# beaconBoard.net
KiCad netlist of a schematic drawn in EAGLE
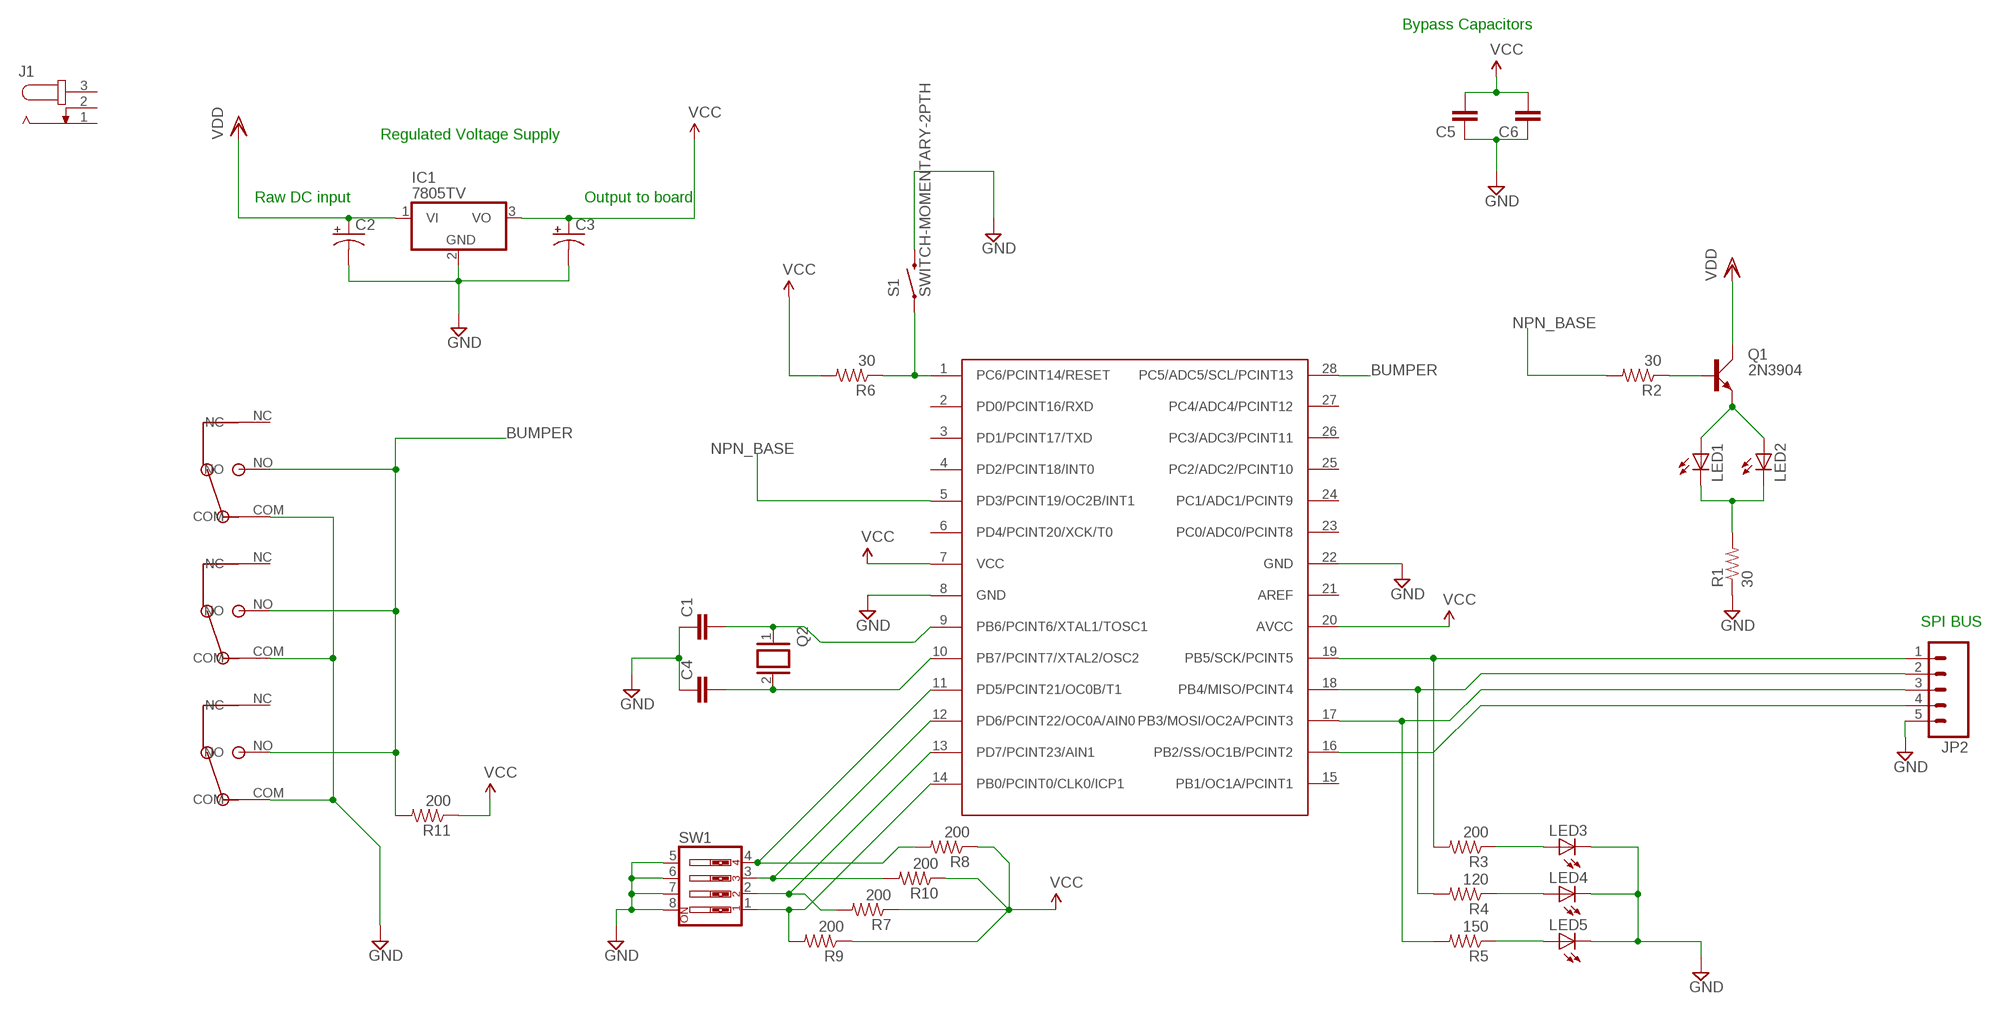
[diagram p0: schematic, sheet 1]

(export (version "E")
  (design (tool "Eeschema 10.0.6"))
  (components
    (comp (ref "C1")
      (value "CAPPTH")
      (footprint "eagle-import:CAP-PTH-SMALL")
      (libsource (lib "eagle-import") (part "CAPPTH"))
    )
    (comp (ref "C2")
      (value "CAP_POLPTH2")
      (footprint "eagle-import:CPOL-RADIAL-10UF-25V")
      (libsource (lib "eagle-import") (part "CAP_POLPTH2"))
    )
    (comp (ref "C3")
      (value "CAP_POLPTH2")
      (footprint "eagle-import:CPOL-RADIAL-10UF-25V")
      (libsource (lib "eagle-import") (part "CAP_POLPTH2"))
    )
    (comp (ref "C4")
      (value "CAPPTH")
      (footprint "eagle-import:CAP-PTH-SMALL")
      (libsource (lib "eagle-import") (part "CAPPTH"))
    )
    (comp (ref "C5")
      (value "CAPPTH")
      (footprint "eagle-import:CAP-PTH-SMALL")
      (libsource (lib "eagle-import") (part "CAPPTH"))
    )
    (comp (ref "C6")
      (value "CAPPTH")
      (footprint "eagle-import:CAP-PTH-SMALL")
      (libsource (lib "eagle-import") (part "CAPPTH"))
    )
    (comp (ref "IC1")
      (value "7805TV")
      (footprint "eagle-import:TO220V")
      (libsource (lib "eagle-import") (part "78TV05"))
    )
    (comp (ref "J1")
      (value "JACK-PLUG1")
      (footprint "eagle-import:SPC4078")
      (libsource (lib "eagle-import") (part "JACK-PLUG1"))
    )
    (comp (ref "JP2")
      (value "M05LOCK_LONGPADS")
      (footprint "eagle-import:1X05_LOCK_LONGPADS")
      (libsource (lib "eagle-import") (part "M05LOCK_LONGPADS"))
    )
    (comp (ref "LED1")
      (value "LED-2AC-CP41B-WES")
      (footprint "eagle-import:CP41B")
      (libsource (lib "eagle-import") (part "LED-2AC-CP41B-WES"))
    )
    (comp (ref "LED2")
      (value "LED-2AC-CP41B-WES")
      (footprint "eagle-import:CP41B")
      (libsource (lib "eagle-import") (part "LED-2AC-CP41B-WES"))
    )
    (comp (ref "LED3")
      (value "LED5MM")
      (footprint "eagle-import:LED5MM")
      (libsource (lib "eagle-import") (part "LED5MM"))
    )
    (comp (ref "LED4")
      (value "LED5MM")
      (footprint "eagle-import:LED5MM")
      (libsource (lib "eagle-import") (part "LED5MM"))
    )
    (comp (ref "LED5")
      (value "LED5MM")
      (footprint "eagle-import:LED5MM")
      (libsource (lib "eagle-import") (part "LED5MM"))
    )
    (comp (ref "Q1")
      (value "2N3904")
      (footprint "eagle-import:TO92D")
      (libsource (lib "eagle-import") (part "2N3904"))
    )
    (comp (ref "Q2")
      (value "XTAL/S")
      (footprint "eagle-import:QS")
      (libsource (lib "eagle-import") (part "XTAL/S"))
    )
    (comp (ref "R1")
      (value "30")
      (footprint "eagle-import:AXIAL-0.4")
      (libsource (lib "eagle-import") (part "RESISTORPTH-1/4W"))
    )
    (comp (ref "R2")
      (value "30")
      (footprint "eagle-import:AXIAL-0.4")
      (libsource (lib "eagle-import") (part "RESISTORPTH-1/4W"))
    )
    (comp (ref "R3")
      (value "200")
      (footprint "eagle-import:AXIAL-0.4")
      (libsource (lib "eagle-import") (part "RESISTORPTH-1/4W"))
    )
    (comp (ref "R4")
      (value "120")
      (footprint "eagle-import:AXIAL-0.4")
      (libsource (lib "eagle-import") (part "RESISTORPTH-1/4W"))
    )
    (comp (ref "R5")
      (value "150")
      (footprint "eagle-import:AXIAL-0.4")
      (libsource (lib "eagle-import") (part "RESISTORPTH-1/4W"))
    )
    (comp (ref "R6")
      (value "30")
      (footprint "eagle-import:AXIAL-0.4")
      (libsource (lib "eagle-import") (part "RESISTORPTH-1/4W"))
    )
    (comp (ref "R7")
      (value "200")
      (footprint "eagle-import:AXIAL-0.4")
      (libsource (lib "eagle-import") (part "RESISTORPTH-1/4W"))
    )
    (comp (ref "R8")
      (value "200")
      (footprint "eagle-import:AXIAL-0.4")
      (libsource (lib "eagle-import") (part "RESISTORPTH-1/4W"))
    )
    (comp (ref "R9")
      (value "200")
      (footprint "eagle-import:AXIAL-0.4")
      (libsource (lib "eagle-import") (part "RESISTORPTH-1/4W"))
    )
    (comp (ref "R10")
      (value "200")
      (footprint "eagle-import:AXIAL-0.4")
      (libsource (lib "eagle-import") (part "RESISTORPTH-1/4W"))
    )
    (comp (ref "R11")
      (value "200")
      (footprint "eagle-import:AXIAL-0.4")
      (libsource (lib "eagle-import") (part "RESISTORPTH-1/4W"))
    )
    (comp (ref "S1")
      (value "SWITCH-MOMENTARY-2PTH")
      (footprint "eagle-import:TACTILE-PTH")
      (libsource (lib "eagle-import") (part "SWITCH-MOMENTARY-2PTH"))
    )
    (comp (ref "SW1")
      (value "SW_DIP-4")
      (footprint "eagle-import:EDG-04")
      (libsource (lib "eagle-import") (part "SW_DIP-4"))
    )
    (comp (ref "U$1")
      (value "DF2-L")
      (footprint "eagle-import:D2F-L")
      (libsource (lib "eagle-import") (part "DF2-L"))
    )
    (comp (ref "U$2")
      (value "DF2-L")
      (footprint "eagle-import:D2F-L")
      (libsource (lib "eagle-import") (part "DF2-L"))
    )
    (comp (ref "U$3")
      (value "DF2-L")
      (footprint "eagle-import:D2F-L")
      (libsource (lib "eagle-import") (part "DF2-L"))
    )
    (comp (ref "U$4")
      (value "ATMEGA328")
      (footprint "eagle-import:DIL28-3")
      (libsource (lib "eagle-import") (part "ATMEGA328"))
    )
  )
  (nets
    (net (code "1") (name "/BUMPER") (class "Default")
      (node (ref "R11") (pin "P$2") (pinfunction "2_P$2") (pintype "passive"))
      (node (ref "U$1") (pin "NO") (pinfunction "NO_NO") (pintype "bidirectional"))
      (node (ref "U$2") (pin "NO") (pinfunction "NO_NO") (pintype "bidirectional"))
      (node (ref "U$3") (pin "NO") (pinfunction "NO_NO") (pintype "bidirectional"))
      (node (ref "U$4") (pin "28") (pinfunction "PC5/ADC5/SCL/PCINT13_28") (pintype "bidirectional"))
    )
    (net (code "2") (name "/NPN_BASE") (class "Default")
      (node (ref "R2") (pin "P$2") (pinfunction "2_P$2") (pintype "passive"))
      (node (ref "U$4") (pin "5") (pinfunction "PD3/PCINT19/OC2B/INT1_5") (pintype "bidirectional"))
    )
    (net (code "3") (name "GND") (class "Default")
      (node (ref "C1") (pin "1") (pinfunction "1_1") (pintype "passive"))
      (node (ref "C2") (pin "2") (pinfunction "-_2") (pintype "passive"))
      (node (ref "C3") (pin "2") (pinfunction "-_2") (pintype "passive"))
      (node (ref "C4") (pin "1") (pinfunction "1_1") (pintype "passive"))
      (node (ref "C5") (pin "1") (pinfunction "1_1") (pintype "passive"))
      (node (ref "C6") (pin "1") (pinfunction "1_1") (pintype "passive"))
      (node (ref "IC1") (pin "2") (pinfunction "GND_2") (pintype "passive"))
      (node (ref "JP2") (pin "5") (pinfunction "5_5") (pintype "passive"))
      (node (ref "LED3") (pin "K") (pinfunction "C_K") (pintype "passive"))
      (node (ref "LED4") (pin "K") (pinfunction "C_K") (pintype "passive"))
      (node (ref "LED5") (pin "K") (pinfunction "C_K") (pintype "passive"))
      (node (ref "R1") (pin "P$1") (pinfunction "1_P$1") (pintype "passive"))
      (node (ref "S1") (pin "3") (pinfunction "2_3") (pintype "passive"))
      (node (ref "SW1") (pin "5") (pinfunction "5_5") (pintype "passive"))
      (node (ref "SW1") (pin "6") (pinfunction "6_6") (pintype "passive"))
      (node (ref "SW1") (pin "7") (pinfunction "7_7") (pintype "passive"))
      (node (ref "SW1") (pin "8") (pinfunction "8_8") (pintype "passive"))
      (node (ref "U$1") (pin "COM") (pinfunction "COM_COM") (pintype "bidirectional"))
      (node (ref "U$2") (pin "COM") (pinfunction "COM_COM") (pintype "bidirectional"))
      (node (ref "U$3") (pin "COM") (pinfunction "COM_COM") (pintype "bidirectional"))
      (node (ref "U$4") (pin "22") (pinfunction "GND_22") (pintype "power_in"))
      (node (ref "U$4") (pin "8") (pinfunction "GND_8") (pintype "power_in"))
    )
    (net (code "4") (name "Net-(LED1-A-Pad2)") (class "Default")
      (node (ref "LED1") (pin "2") (pinfunction "A_2") (pintype "passive"))
      (node (ref "LED1") (pin "3") (pinfunction "A_3") (pintype "passive"))
      (node (ref "LED2") (pin "2") (pinfunction "A_2") (pintype "passive"))
      (node (ref "LED2") (pin "3") (pinfunction "A_3") (pintype "passive"))
      (node (ref "Q1") (pin "E") (pinfunction "E_E") (pintype "passive"))
    )
    (net (code "5") (name "Net-(R1-2)") (class "Default")
      (node (ref "LED1") (pin "1") (pinfunction "C_1") (pintype "passive"))
      (node (ref "LED1") (pin "4") (pinfunction "C_4") (pintype "passive"))
      (node (ref "LED2") (pin "1") (pinfunction "C_1") (pintype "passive"))
      (node (ref "LED2") (pin "4") (pinfunction "C_4") (pintype "passive"))
      (node (ref "R1") (pin "P$2") (pinfunction "2_P$2") (pintype "passive"))
    )
    (net (code "6") (name "Net-(R2-1)") (class "Default")
      (node (ref "Q1") (pin "B") (pinfunction "B_B") (pintype "passive"))
      (node (ref "R2") (pin "P$1") (pinfunction "1_P$1") (pintype "passive"))
    )
    (net (code "7") (name "Net-(R3-1)") (class "Default")
      (node (ref "LED3") (pin "A") (pinfunction "A_A") (pintype "passive"))
      (node (ref "R3") (pin "P$1") (pinfunction "1_P$1") (pintype "passive"))
    )
    (net (code "8") (name "Net-(R3-2)") (class "Default")
      (node (ref "JP2") (pin "1") (pinfunction "1_1") (pintype "passive"))
      (node (ref "R3") (pin "P$2") (pinfunction "2_P$2") (pintype "passive"))
      (node (ref "U$4") (pin "19") (pinfunction "PB5/SCK/PCINT5_19") (pintype "bidirectional"))
    )
    (net (code "9") (name "Net-(R4-1)") (class "Default")
      (node (ref "LED4") (pin "A") (pinfunction "A_A") (pintype "passive"))
      (node (ref "R4") (pin "P$1") (pinfunction "1_P$1") (pintype "passive"))
    )
    (net (code "10") (name "Net-(R4-2)") (class "Default")
      (node (ref "JP2") (pin "2") (pinfunction "2_2") (pintype "passive"))
      (node (ref "R4") (pin "P$2") (pinfunction "2_P$2") (pintype "passive"))
      (node (ref "U$4") (pin "18") (pinfunction "PB4/MISO/PCINT4_18") (pintype "bidirectional"))
    )
    (net (code "11") (name "Net-(R5-1)") (class "Default")
      (node (ref "LED5") (pin "A") (pinfunction "A_A") (pintype "passive"))
      (node (ref "R5") (pin "P$1") (pinfunction "1_P$1") (pintype "passive"))
    )
    (net (code "12") (name "Net-(R5-2)") (class "Default")
      (node (ref "JP2") (pin "3") (pinfunction "3_3") (pintype "passive"))
      (node (ref "R5") (pin "P$2") (pinfunction "2_P$2") (pintype "passive"))
      (node (ref "U$4") (pin "17") (pinfunction "PB3/MOSI/OC2A/PCINT3_17") (pintype "bidirectional"))
    )
    (net (code "13") (name "Net-(R6-1)") (class "Default")
      (node (ref "R6") (pin "P$1") (pinfunction "1_P$1") (pintype "passive"))
      (node (ref "S1") (pin "1") (pinfunction "1_1") (pintype "passive"))
      (node (ref "U$4") (pin "1") (pinfunction "PC6/PCINT14/RESET_1") (pintype "bidirectional"))
    )
    (net (code "14") (name "Net-(R7-2)") (class "Default")
      (node (ref "R7") (pin "P$2") (pinfunction "2_P$2") (pintype "passive"))
      (node (ref "SW1") (pin "2") (pinfunction "2_2") (pintype "passive"))
      (node (ref "U$4") (pin "13") (pinfunction "PD7/PCINT23/AIN1_13") (pintype "bidirectional"))
    )
    (net (code "15") (name "Net-(R8-2)") (class "Default")
      (node (ref "R8") (pin "P$2") (pinfunction "2_P$2") (pintype "passive"))
      (node (ref "SW1") (pin "4") (pinfunction "4_4") (pintype "passive"))
      (node (ref "U$4") (pin "11") (pinfunction "PD5/PCINT21/OC0B/T1_11") (pintype "bidirectional"))
    )
    (net (code "16") (name "Net-(R9-2)") (class "Default")
      (node (ref "R9") (pin "P$2") (pinfunction "2_P$2") (pintype "passive"))
      (node (ref "SW1") (pin "1") (pinfunction "1_1") (pintype "passive"))
      (node (ref "U$4") (pin "14") (pinfunction "PB0/PCINT0/CLK0/ICP1_14") (pintype "bidirectional"))
    )
    (net (code "17") (name "Net-(R10-2)") (class "Default")
      (node (ref "R10") (pin "P$2") (pinfunction "2_P$2") (pintype "passive"))
      (node (ref "SW1") (pin "3") (pinfunction "3_3") (pintype "passive"))
      (node (ref "U$4") (pin "12") (pinfunction "PD6/PCINT22/OC0A/AIN0_12") (pintype "bidirectional"))
    )
    (net (code "18") (name "Net-(U$4-PB2{slash}SS{slash}OC1B{slash}PCINT2)") (class "Default")
      (node (ref "JP2") (pin "4") (pinfunction "4_4") (pintype "passive"))
      (node (ref "U$4") (pin "16") (pinfunction "PB2/SS/OC1B/PCINT2_16") (pintype "bidirectional"))
    )
    (net (code "19") (name "Net-(U$4-PB6{slash}PCINT6{slash}XTAL1{slash}TOSC1)") (class "Default")
      (node (ref "C1") (pin "2") (pinfunction "2_2") (pintype "passive"))
      (node (ref "Q2") (pin "1") (pinfunction "1_1") (pintype "passive"))
      (node (ref "U$4") (pin "9") (pinfunction "PB6/PCINT6/XTAL1/TOSC1_9") (pintype "bidirectional"))
    )
    (net (code "20") (name "Net-(U$4-PB7{slash}PCINT7{slash}XTAL2{slash}OSC2)") (class "Default")
      (node (ref "C4") (pin "2") (pinfunction "2_2") (pintype "passive"))
      (node (ref "Q2") (pin "2") (pinfunction "2_2") (pintype "passive"))
      (node (ref "U$4") (pin "10") (pinfunction "PB7/PCINT7/XTAL2/OSC2_10") (pintype "bidirectional"))
    )
    (net (code "21") (name "VCC") (class "Default")
      (node (ref "C3") (pin "1") (pinfunction "+_1") (pintype "passive"))
      (node (ref "C5") (pin "2") (pinfunction "2_2") (pintype "passive"))
      (node (ref "C6") (pin "2") (pinfunction "2_2") (pintype "passive"))
      (node (ref "IC1") (pin "3") (pinfunction "VO_3") (pintype "passive"))
      (node (ref "R10") (pin "P$1") (pinfunction "1_P$1") (pintype "passive"))
      (node (ref "R11") (pin "P$1") (pinfunction "1_P$1") (pintype "passive"))
      (node (ref "R6") (pin "P$2") (pinfunction "2_P$2") (pintype "passive"))
      (node (ref "R7") (pin "P$1") (pinfunction "1_P$1") (pintype "passive"))
      (node (ref "R8") (pin "P$1") (pinfunction "1_P$1") (pintype "passive"))
      (node (ref "R9") (pin "P$1") (pinfunction "1_P$1") (pintype "passive"))
      (node (ref "U$4") (pin "20") (pinfunction "AVCC_20") (pintype "bidirectional"))
      (node (ref "U$4") (pin "7") (pinfunction "VCC_7") (pintype "power_in"))
    )
    (net (code "22") (name "VDD") (class "Default")
      (node (ref "C2") (pin "1") (pinfunction "+_1") (pintype "passive"))
      (node (ref "IC1") (pin "1") (pinfunction "VI_1") (pintype "input"))
      (node (ref "Q1") (pin "C") (pinfunction "C_C") (pintype "passive"))
    )
    (net (code "23") (name "unconnected-(J1-Pad1)") (class "Default")
      (node (ref "J1") (pin "1") (pinfunction "1_1") (pintype "passive"))
    )
    (net (code "24") (name "unconnected-(J1-Pad2)") (class "Default")
      (node (ref "J1") (pin "2") (pinfunction "2_2") (pintype "passive"))
    )
    (net (code "25") (name "unconnected-(J1-Pad3)") (class "Default")
      (node (ref "J1") (pin "3") (pinfunction "3_3") (pintype "passive"))
    )
    (net (code "26") (name "unconnected-(U$1-PadNC)") (class "Default")
      (node (ref "U$1") (pin "NC") (pinfunction "NC_NC") (pintype "bidirectional"))
    )
    (net (code "27") (name "unconnected-(U$2-PadNC)") (class "Default")
      (node (ref "U$2") (pin "NC") (pinfunction "NC_NC") (pintype "bidirectional"))
    )
    (net (code "28") (name "unconnected-(U$3-PadNC)") (class "Default")
      (node (ref "U$3") (pin "NC") (pinfunction "NC_NC") (pintype "bidirectional"))
    )
    (net (code "29") (name "unconnected-(U$4-AREF-Pad21)") (class "Default")
      (node (ref "U$4") (pin "21") (pinfunction "AREF_21") (pintype "bidirectional"))
    )
    (net (code "30") (name "unconnected-(U$4-PB1{slash}OC1A{slash}PCINT1-Pad15)") (class "Default")
      (node (ref "U$4") (pin "15") (pinfunction "PB1/OC1A/PCINT1_15") (pintype "bidirectional"))
    )
    (net (code "31") (name "unconnected-(U$4-PC0{slash}ADC0{slash}PCINT8-Pad23)") (class "Default")
      (node (ref "U$4") (pin "23") (pinfunction "PC0/ADC0/PCINT8_23") (pintype "bidirectional"))
    )
    (net (code "32") (name "unconnected-(U$4-PC1{slash}ADC1{slash}PCINT9-Pad24)") (class "Default")
      (node (ref "U$4") (pin "24") (pinfunction "PC1/ADC1/PCINT9_24") (pintype "bidirectional"))
    )
    (net (code "33") (name "unconnected-(U$4-PC2{slash}ADC2{slash}PCINT10-Pad25)") (class "Default")
      (node (ref "U$4") (pin "25") (pinfunction "PC2/ADC2/PCINT10_25") (pintype "bidirectional"))
    )
    (net (code "34") (name "unconnected-(U$4-PC3{slash}ADC3{slash}PCINT11-Pad26)") (class "Default")
      (node (ref "U$4") (pin "26") (pinfunction "PC3/ADC3/PCINT11_26") (pintype "bidirectional"))
    )
    (net (code "35") (name "unconnected-(U$4-PC4{slash}ADC4{slash}PCINT12-Pad27)") (class "Default")
      (node (ref "U$4") (pin "27") (pinfunction "PC4/ADC4/PCINT12_27") (pintype "bidirectional"))
    )
    (net (code "36") (name "unconnected-(U$4-PD0{slash}PCINT16{slash}RXD-Pad2)") (class "Default")
      (node (ref "U$4") (pin "2") (pinfunction "PD0/PCINT16/RXD_2") (pintype "bidirectional"))
    )
    (net (code "37") (name "unconnected-(U$4-PD1{slash}PCINT17{slash}TXD-Pad3)") (class "Default")
      (node (ref "U$4") (pin "3") (pinfunction "PD1/PCINT17/TXD_3") (pintype "bidirectional"))
    )
    (net (code "38") (name "unconnected-(U$4-PD2{slash}PCINT18{slash}INT0-Pad4)") (class "Default")
      (node (ref "U$4") (pin "4") (pinfunction "PD2/PCINT18/INT0_4") (pintype "bidirectional"))
    )
    (net (code "39") (name "unconnected-(U$4-PD4{slash}PCINT20{slash}XCK{slash}T0-Pad6)") (class "Default")
      (node (ref "U$4") (pin "6") (pinfunction "PD4/PCINT20/XCK/T0_6") (pintype "bidirectional"))
    )
  )
)
